# SOT-23-5_Breakout_Board.net
KiCad netlist of a schematic drawn in EAGLE
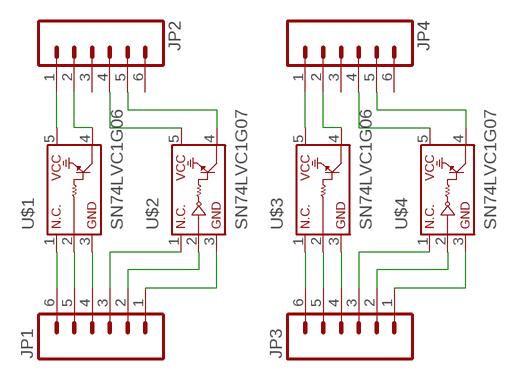
[diagram p0: schematic, sheet 1]

(export (version "E")
  (design (tool "Eeschema 10.0.6"))
  (components
    (comp (ref "JP1")
      (value "M06")
      (footprint "eagle-import:1X06")
      (libsource (lib "eagle-import") (part "M06"))
    )
    (comp (ref "JP2")
      (value "M06")
      (footprint "eagle-import:1X06")
      (libsource (lib "eagle-import") (part "M06"))
    )
    (comp (ref "JP3")
      (value "M06")
      (footprint "eagle-import:1X06")
      (libsource (lib "eagle-import") (part "M06"))
    )
    (comp (ref "JP4")
      (value "M06")
      (footprint "eagle-import:1X06")
      (libsource (lib "eagle-import") (part "M06"))
    )
    (comp (ref "U$1")
      (value "SN74LVC1G06")
      (footprint "eagle-import:SOT-23-5")
      (libsource (lib "eagle-import") (part "SN74LVC1G06"))
    )
    (comp (ref "U$2")
      (value "SN74LVC1G07")
      (footprint "eagle-import:SOT-23-5")
      (libsource (lib "eagle-import") (part "SN74LVC1G07"))
    )
    (comp (ref "U$3")
      (value "SN74LVC1G06")
      (footprint "eagle-import:SOT-23-5")
      (libsource (lib "eagle-import") (part "SN74LVC1G06"))
    )
    (comp (ref "U$4")
      (value "SN74LVC1G07")
      (footprint "eagle-import:SOT-23-5")
      (libsource (lib "eagle-import") (part "SN74LVC1G07"))
    )
  )
  (nets
    (net (code "1") (name "Net-(JP1-Pad1)") (class "Default")
      (node (ref "JP1") (pin "1") (pinfunction "1_1") (pintype "passive"))
      (node (ref "U$2") (pin "3") (pinfunction "3_3") (pintype "passive"))
    )
    (net (code "2") (name "Net-(JP1-Pad2)") (class "Default")
      (node (ref "JP1") (pin "2") (pinfunction "2_2") (pintype "passive"))
      (node (ref "U$2") (pin "2") (pinfunction "2_2") (pintype "passive"))
    )
    (net (code "3") (name "Net-(JP1-Pad3)") (class "Default")
      (node (ref "JP1") (pin "3") (pinfunction "3_3") (pintype "passive"))
      (node (ref "U$2") (pin "1") (pinfunction "1_1") (pintype "passive"))
    )
    (net (code "4") (name "Net-(JP1-Pad4)") (class "Default")
      (node (ref "JP1") (pin "4") (pinfunction "4_4") (pintype "passive"))
      (node (ref "U$1") (pin "3") (pinfunction "3_3") (pintype "passive"))
    )
    (net (code "5") (name "Net-(JP1-Pad5)") (class "Default")
      (node (ref "JP1") (pin "5") (pinfunction "5_5") (pintype "passive"))
      (node (ref "U$1") (pin "2") (pinfunction "2_2") (pintype "passive"))
    )
    (net (code "6") (name "Net-(JP1-Pad6)") (class "Default")
      (node (ref "JP1") (pin "6") (pinfunction "6_6") (pintype "passive"))
      (node (ref "U$1") (pin "1") (pinfunction "1_1") (pintype "passive"))
    )
    (net (code "7") (name "Net-(JP2-Pad1)") (class "Default")
      (node (ref "JP2") (pin "1") (pinfunction "1_1") (pintype "passive"))
      (node (ref "U$1") (pin "5") (pinfunction "5_5") (pintype "passive"))
    )
    (net (code "8") (name "Net-(JP2-Pad2)") (class "Default")
      (node (ref "JP2") (pin "2") (pinfunction "2_2") (pintype "passive"))
      (node (ref "U$1") (pin "4") (pinfunction "4_4") (pintype "passive"))
    )
    (net (code "9") (name "Net-(JP2-Pad4)") (class "Default")
      (node (ref "JP2") (pin "4") (pinfunction "4_4") (pintype "passive"))
      (node (ref "U$2") (pin "5") (pinfunction "5_5") (pintype "passive"))
    )
    (net (code "10") (name "Net-(JP2-Pad5)") (class "Default")
      (node (ref "JP2") (pin "5") (pinfunction "5_5") (pintype "passive"))
      (node (ref "U$2") (pin "4") (pinfunction "4_4") (pintype "passive"))
    )
    (net (code "11") (name "Net-(JP3-Pad1)") (class "Default")
      (node (ref "JP3") (pin "1") (pinfunction "1_1") (pintype "passive"))
      (node (ref "U$4") (pin "3") (pinfunction "3_3") (pintype "passive"))
    )
    (net (code "12") (name "Net-(JP3-Pad2)") (class "Default")
      (node (ref "JP3") (pin "2") (pinfunction "2_2") (pintype "passive"))
      (node (ref "U$4") (pin "2") (pinfunction "2_2") (pintype "passive"))
    )
    (net (code "13") (name "Net-(JP3-Pad3)") (class "Default")
      (node (ref "JP3") (pin "3") (pinfunction "3_3") (pintype "passive"))
      (node (ref "U$4") (pin "1") (pinfunction "1_1") (pintype "passive"))
    )
    (net (code "14") (name "Net-(JP3-Pad4)") (class "Default")
      (node (ref "JP3") (pin "4") (pinfunction "4_4") (pintype "passive"))
      (node (ref "U$3") (pin "3") (pinfunction "3_3") (pintype "passive"))
    )
    (net (code "15") (name "Net-(JP3-Pad5)") (class "Default")
      (node (ref "JP3") (pin "5") (pinfunction "5_5") (pintype "passive"))
      (node (ref "U$3") (pin "2") (pinfunction "2_2") (pintype "passive"))
    )
    (net (code "16") (name "Net-(JP3-Pad6)") (class "Default")
      (node (ref "JP3") (pin "6") (pinfunction "6_6") (pintype "passive"))
      (node (ref "U$3") (pin "1") (pinfunction "1_1") (pintype "passive"))
    )
    (net (code "17") (name "Net-(JP4-Pad1)") (class "Default")
      (node (ref "JP4") (pin "1") (pinfunction "1_1") (pintype "passive"))
      (node (ref "U$3") (pin "5") (pinfunction "5_5") (pintype "passive"))
    )
    (net (code "18") (name "Net-(JP4-Pad2)") (class "Default")
      (node (ref "JP4") (pin "2") (pinfunction "2_2") (pintype "passive"))
      (node (ref "U$3") (pin "4") (pinfunction "4_4") (pintype "passive"))
    )
    (net (code "19") (name "Net-(JP4-Pad4)") (class "Default")
      (node (ref "JP4") (pin "4") (pinfunction "4_4") (pintype "passive"))
      (node (ref "U$4") (pin "5") (pinfunction "5_5") (pintype "passive"))
    )
    (net (code "20") (name "Net-(JP4-Pad5)") (class "Default")
      (node (ref "JP4") (pin "5") (pinfunction "5_5") (pintype "passive"))
      (node (ref "U$4") (pin "4") (pinfunction "4_4") (pintype "passive"))
    )
    (net (code "21") (name "unconnected-(JP2-Pad3)") (class "Default")
      (node (ref "JP2") (pin "3") (pinfunction "3_3") (pintype "passive"))
    )
    (net (code "22") (name "unconnected-(JP2-Pad6)") (class "Default")
      (node (ref "JP2") (pin "6") (pinfunction "6_6") (pintype "passive"))
    )
    (net (code "23") (name "unconnected-(JP4-Pad3)") (class "Default")
      (node (ref "JP4") (pin "3") (pinfunction "3_3") (pintype "passive"))
    )
    (net (code "24") (name "unconnected-(JP4-Pad6)") (class "Default")
      (node (ref "JP4") (pin "6") (pinfunction "6_6") (pintype "passive"))
    )
  )
)
